# SingleLight.net
KiCad netlist of a schematic drawn in EAGLE
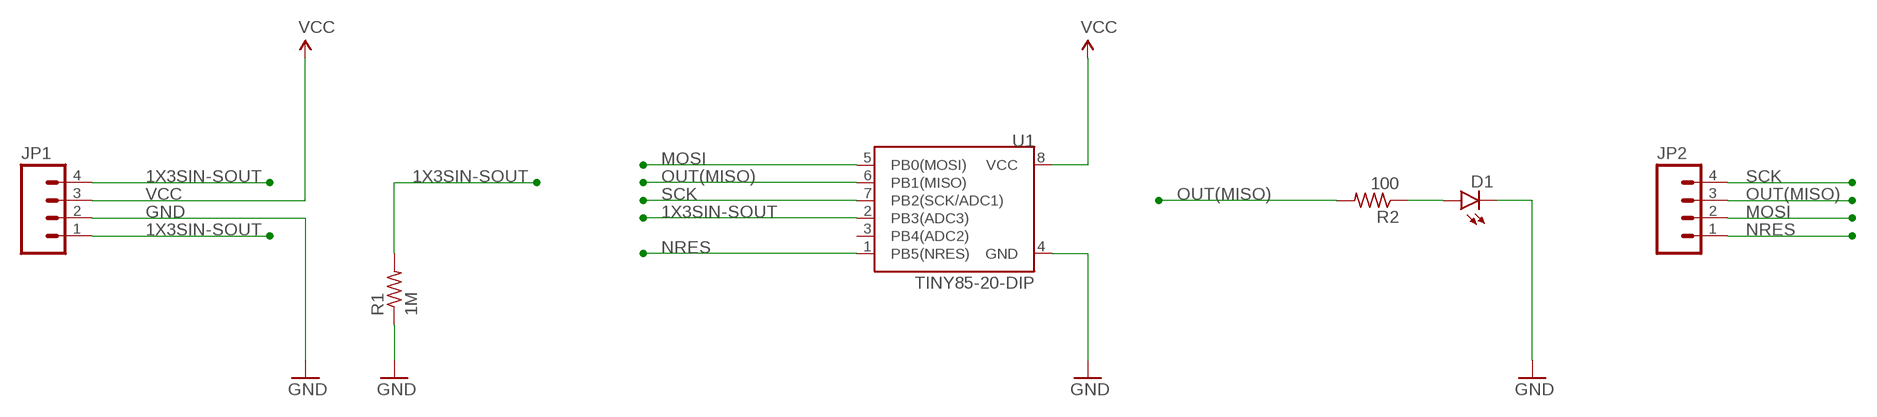
[diagram p0: schematic, sheet 1]

(export (version "E")
  (design (tool "Eeschema 10.0.6"))
  (components
    (comp (ref "D1")
      (value "LED5MM")
      (footprint "eagle-import:LED5MM")
      (libsource (lib "eagle-import") (part "LED5MM"))
    )
    (comp (ref "JP1")
      (value "M04PTH")
      (footprint "eagle-import:1X04")
      (libsource (lib "eagle-import") (part "M04PTH"))
    )
    (comp (ref "JP2")
      (value "M04PTH")
      (footprint "eagle-import:1X04")
      (libsource (lib "eagle-import") (part "M04PTH"))
    )
    (comp (ref "R1")
      (value "1M")
      (footprint "eagle-import:R0603")
      (libsource (lib "eagle-import") (part "R-US_R0603"))
    )
    (comp (ref "R2")
      (value "100")
      (footprint "eagle-import:R0603")
      (libsource (lib "eagle-import") (part "R-US_R0603"))
    )
    (comp (ref "U1")
      (value "TINY85-20-DIP")
      (footprint "eagle-import:DIP08")
      (libsource (lib "eagle-import") (part "ATTINY45TINY85-20-DIP"))
    )
  )
  (nets
    (net (code "1") (name "/1X3SIN-SOUT") (class "Default")
      (node (ref "JP1") (pin "1") (pinfunction "1_1") (pintype "passive"))
      (node (ref "JP1") (pin "4") (pinfunction "4_4") (pintype "passive"))
      (node (ref "R1") (pin "2") (pinfunction "2_2") (pintype "passive"))
      (node (ref "U1") (pin "2") (pinfunction "PB3(ADC3)_2") (pintype "bidirectional"))
    )
    (net (code "2") (name "/MOSI") (class "Default")
      (node (ref "JP2") (pin "2") (pinfunction "2_2") (pintype "passive"))
      (node (ref "U1") (pin "5") (pinfunction "PB0(MOSI)_5") (pintype "bidirectional"))
    )
    (net (code "3") (name "/NRES") (class "Default")
      (node (ref "JP2") (pin "1") (pinfunction "1_1") (pintype "passive"))
      (node (ref "U1") (pin "1") (pinfunction "PB5(NRES)_1") (pintype "bidirectional"))
    )
    (net (code "4") (name "/OUT(MISO)") (class "Default")
      (node (ref "JP2") (pin "3") (pinfunction "3_3") (pintype "passive"))
      (node (ref "R2") (pin "2") (pinfunction "2_2") (pintype "passive"))
      (node (ref "U1") (pin "6") (pinfunction "PB1(MISO)_6") (pintype "bidirectional"))
    )
    (net (code "5") (name "/SCK") (class "Default")
      (node (ref "JP2") (pin "4") (pinfunction "4_4") (pintype "passive"))
      (node (ref "U1") (pin "7") (pinfunction "PB2(SCK/ADC1)_7") (pintype "bidirectional"))
    )
    (net (code "6") (name "GND") (class "Default")
      (node (ref "D1") (pin "K") (pinfunction "C_K") (pintype "passive"))
      (node (ref "JP1") (pin "2") (pinfunction "2_2") (pintype "passive"))
      (node (ref "R1") (pin "1") (pinfunction "1_1") (pintype "passive"))
      (node (ref "U1") (pin "4") (pinfunction "GND_4") (pintype "bidirectional"))
    )
    (net (code "7") (name "Net-(D1-PadA)") (class "Default")
      (node (ref "D1") (pin "A") (pinfunction "A_A") (pintype "passive"))
      (node (ref "R2") (pin "1") (pinfunction "1_1") (pintype "passive"))
    )
    (net (code "8") (name "VCC") (class "Default")
      (node (ref "JP1") (pin "3") (pinfunction "3_3") (pintype "passive"))
      (node (ref "U1") (pin "8") (pinfunction "VCC_8") (pintype "bidirectional"))
    )
    (net (code "9") (name "unconnected-(U1-PB4(ADC2)-Pad3)") (class "Default")
      (node (ref "U1") (pin "3") (pinfunction "PB4(ADC2)_3") (pintype "bidirectional"))
    )
  )
)
